# CC3200_Breakout.net
KiCad netlist of a schematic drawn in EAGLE
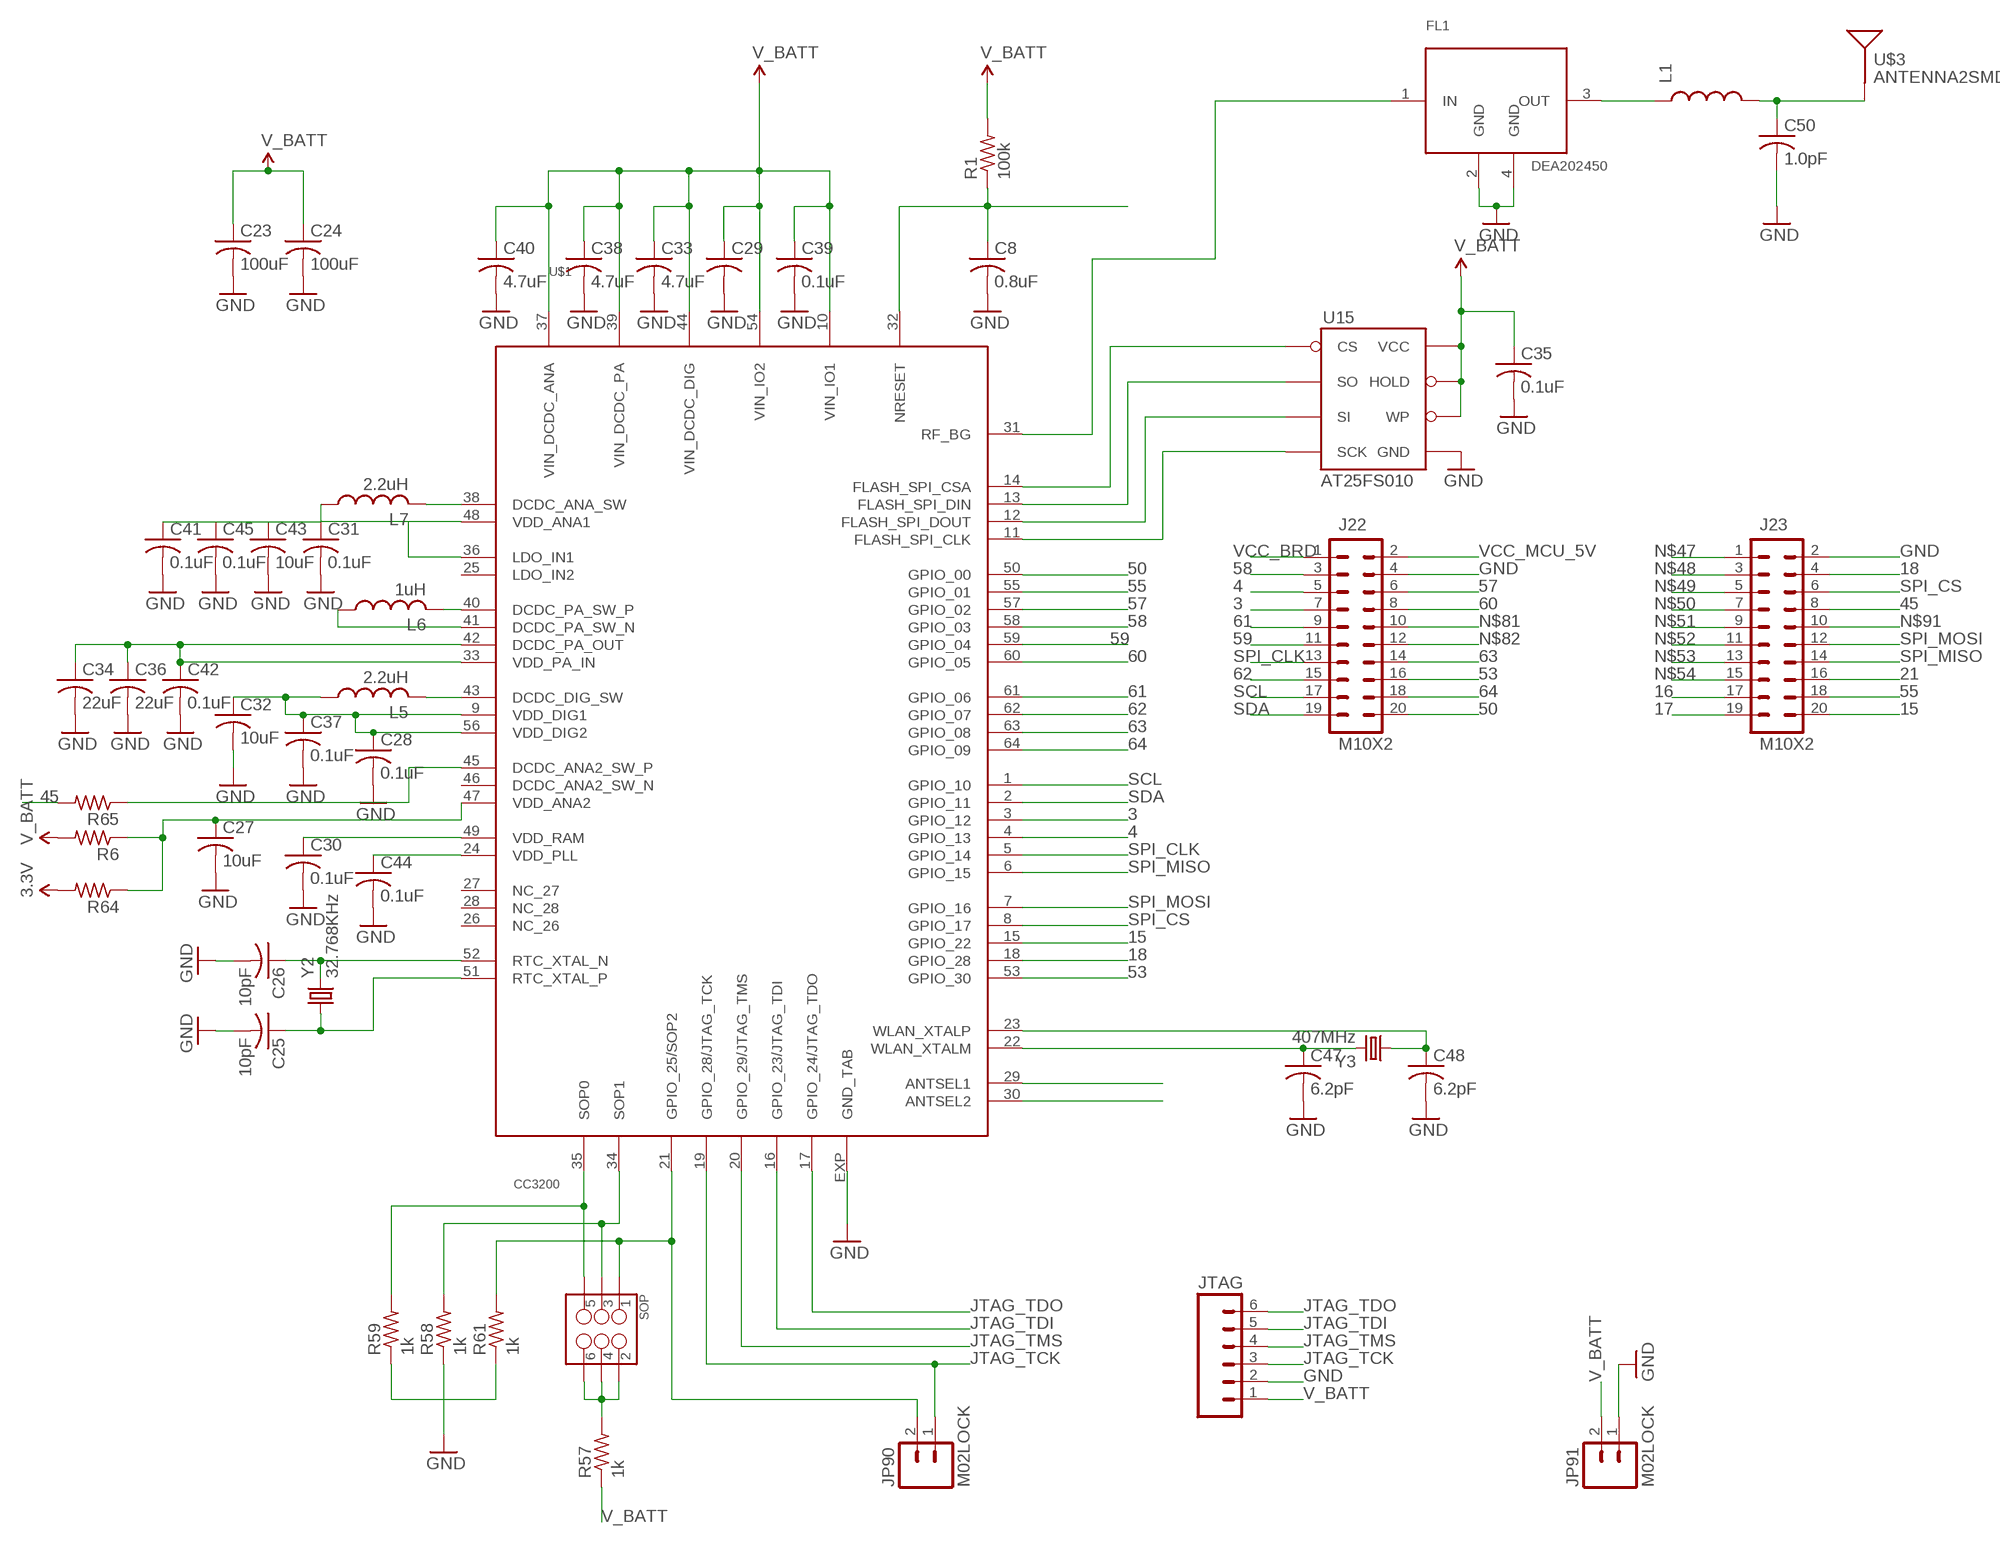
[diagram p0: schematic, sheet 1]

(export (version "E")
  (design (tool "Eeschema 10.0.6"))
  (components
    (comp (ref "C8")
      (value "0.8uF")
      (footprint "eagle-import:C0402K")
      (libsource (lib "eagle-import") (part "C-USC0402K"))
    )
    (comp (ref "C23")
      (value "100uF")
      (footprint "eagle-import:C0402K")
      (libsource (lib "eagle-import") (part "C-USC0402K"))
    )
    (comp (ref "C24")
      (value "100uF")
      (footprint "eagle-import:C0402K")
      (libsource (lib "eagle-import") (part "C-USC0402K"))
    )
    (comp (ref "C25")
      (value "10pF")
      (footprint "eagle-import:C0402K")
      (libsource (lib "eagle-import") (part "C-USC0402K"))
    )
    (comp (ref "C26")
      (value "10pF")
      (footprint "eagle-import:C0402K")
      (libsource (lib "eagle-import") (part "C-USC0402K"))
    )
    (comp (ref "C27")
      (value "10uF")
      (footprint "eagle-import:C0402K")
      (libsource (lib "eagle-import") (part "C-USC0402K"))
    )
    (comp (ref "C28")
      (value "0.1uF")
      (footprint "eagle-import:C0402K")
      (libsource (lib "eagle-import") (part "C-USC0402K"))
    )
    (comp (ref "C29")
      (value "C-USC0402K")
      (footprint "eagle-import:C0402K")
      (libsource (lib "eagle-import") (part "C-USC0402K"))
    )
    (comp (ref "C30")
      (value "0.1uF")
      (footprint "eagle-import:C0402K")
      (libsource (lib "eagle-import") (part "C-USC0402K"))
    )
    (comp (ref "C31")
      (value "0.1uF")
      (footprint "eagle-import:C0402K")
      (libsource (lib "eagle-import") (part "C-USC0402K"))
    )
    (comp (ref "C32")
      (value "10uF")
      (footprint "eagle-import:C0402K")
      (libsource (lib "eagle-import") (part "C-USC0402K"))
    )
    (comp (ref "C33")
      (value "4.7uF")
      (footprint "eagle-import:C0402K")
      (libsource (lib "eagle-import") (part "C-USC0402K"))
    )
    (comp (ref "C34")
      (value "22uF")
      (footprint "eagle-import:C0402K")
      (libsource (lib "eagle-import") (part "C-USC0402K"))
    )
    (comp (ref "C35")
      (value "0.1uF")
      (footprint "eagle-import:C0402K")
      (libsource (lib "eagle-import") (part "C-USC0402K"))
    )
    (comp (ref "C36")
      (value "22uF")
      (footprint "eagle-import:C0402K")
      (libsource (lib "eagle-import") (part "C-USC0402K"))
    )
    (comp (ref "C37")
      (value "0.1uF")
      (footprint "eagle-import:C0402K")
      (libsource (lib "eagle-import") (part "C-USC0402K"))
    )
    (comp (ref "C38")
      (value "4.7uF")
      (footprint "eagle-import:C0402K")
      (libsource (lib "eagle-import") (part "C-USC0402K"))
    )
    (comp (ref "C39")
      (value "0.1uF")
      (footprint "eagle-import:C0402K")
      (libsource (lib "eagle-import") (part "C-USC0402K"))
    )
    (comp (ref "C40")
      (value "4.7uF")
      (footprint "eagle-import:C0402K")
      (libsource (lib "eagle-import") (part "C-USC0402K"))
    )
    (comp (ref "C41")
      (value "0.1uF")
      (footprint "eagle-import:C0402K")
      (libsource (lib "eagle-import") (part "C-USC0402K"))
    )
    (comp (ref "C42")
      (value "0.1uF")
      (footprint "eagle-import:C0402K")
      (libsource (lib "eagle-import") (part "C-USC0402K"))
    )
    (comp (ref "C43")
      (value "10uF")
      (footprint "eagle-import:C0402K")
      (libsource (lib "eagle-import") (part "C-USC0402K"))
    )
    (comp (ref "C44")
      (value "0.1uF")
      (footprint "eagle-import:C0402K")
      (libsource (lib "eagle-import") (part "C-USC0402K"))
    )
    (comp (ref "C45")
      (value "0.1uF")
      (footprint "eagle-import:C0402K")
      (libsource (lib "eagle-import") (part "C-USC0402K"))
    )
    (comp (ref "C47")
      (value "6.2pF")
      (footprint "eagle-import:C0402K")
      (libsource (lib "eagle-import") (part "C-USC0402K"))
    )
    (comp (ref "C48")
      (value "6.2pF")
      (footprint "eagle-import:C0402K")
      (libsource (lib "eagle-import") (part "C-USC0402K"))
    )
    (comp (ref "C50")
      (value "1.0pF")
      (footprint "eagle-import:C0402K")
      (libsource (lib "eagle-import") (part "C-USC0402K"))
    )
    (comp (ref "FL1")
      (value "DEA202450")
      (footprint "eagle-import:DEA202450")
      (libsource (lib "eagle-import") (part "DEA202450"))
    )
    (comp (ref "J22")
      (value "M10X2")
      (footprint "eagle-import:2X10")
      (libsource (lib "eagle-import") (part "M10X2"))
    )
    (comp (ref "J23")
      (value "M10X2")
      (footprint "eagle-import:2X10")
      (libsource (lib "eagle-import") (part "M10X2"))
    )
    (comp (ref "JP90")
      (value "M02LOCK")
      (footprint "eagle-import:1X02_LOCK")
      (libsource (lib "eagle-import") (part "M02LOCK"))
    )
    (comp (ref "JP91")
      (value "M02LOCK")
      (footprint "eagle-import:1X02_LOCK")
      (libsource (lib "eagle-import") (part "M02LOCK"))
    )
    (comp (ref "JTAG")
      (value "M06SILK_FEMALE_PTH")
      (footprint "eagle-import:1X06")
      (libsource (lib "eagle-import") (part "M06SILK_FEMALE_PTH"))
    )
    (comp (ref "L1")
      (value "INDUCTOR-SPARKFUN0402")
      (footprint "eagle-import:C0402")
      (libsource (lib "eagle-import") (part "INDUCTOR-SPARKFUN0402"))
    )
    (comp (ref "L5")
      (value "2.2uH")
      (footprint "eagle-import:L2012C")
      (libsource (lib "eagle-import") (part "L-USL2012C"))
    )
    (comp (ref "L6")
      (value "1uH")
      (footprint "eagle-import:L2012C")
      (libsource (lib "eagle-import") (part "L-USL2012C"))
    )
    (comp (ref "L7")
      (value "2.2uH")
      (footprint "eagle-import:L2012C")
      (libsource (lib "eagle-import") (part "L-USL2012C"))
    )
    (comp (ref "R1")
      (value "100k")
      (footprint "eagle-import:R0402")
      (libsource (lib "eagle-import") (part "R-US_R0402"))
    )
    (comp (ref "R6")
      (value "R-US_R0402")
      (footprint "eagle-import:R0402")
      (libsource (lib "eagle-import") (part "R-US_R0402"))
    )
    (comp (ref "R57")
      (value "1k")
      (footprint "eagle-import:R0402")
      (libsource (lib "eagle-import") (part "R-US_R0402"))
    )
    (comp (ref "R58")
      (value "1k")
      (footprint "eagle-import:R0402")
      (libsource (lib "eagle-import") (part "R-US_R0402"))
    )
    (comp (ref "R59")
      (value "1k")
      (footprint "eagle-import:R0402")
      (libsource (lib "eagle-import") (part "R-US_R0402"))
    )
    (comp (ref "R61")
      (value "1k")
      (footprint "eagle-import:R0402")
      (libsource (lib "eagle-import") (part "R-US_R0402"))
    )
    (comp (ref "R64")
      (value "R-US_R0402")
      (footprint "eagle-import:R0402")
      (libsource (lib "eagle-import") (part "R-US_R0402"))
    )
    (comp (ref "R65")
      (value "R-US_R0402")
      (footprint "eagle-import:R0402")
      (libsource (lib "eagle-import") (part "R-US_R0402"))
    )
    (comp (ref "SOP")
      (value "M03X22X3_SILK_MALE_PTH")
      (footprint "eagle-import:2X3")
      (libsource (lib "eagle-import") (part "M03X22X3_SILK_MALE_PTH"))
    )
    (comp (ref "U$1")
      (value "CC3200")
      (footprint "eagle-import:PVQFN-N64")
      (libsource (lib "eagle-import") (part "CC3200"))
    )
    (comp (ref "U$3")
      (value "ANTENNA2SMD")
      (footprint "eagle-import:ANTENNA-CHIP2")
      (libsource (lib "eagle-import") (part "ANTENNA2SMD"))
    )
    (comp (ref "U15")
      (value "AT25FS010")
      (footprint "eagle-import:SO08WIDE")
      (libsource (lib "eagle-import") (part "AT25FS010"))
    )
    (comp (ref "Y2")
      (value "32.768KHz")
      (footprint "eagle-import:CRYSTAL-SMD-5X3")
      (libsource (lib "eagle-import") (part "CRYSTAL5X3"))
    )
    (comp (ref "Y3")
      (value "407MHz")
      (footprint "eagle-import:CRYSTAL-SMD-5X3")
      (libsource (lib "eagle-import") (part "CRYSTAL5X3"))
    )
  )
  (nets
    (net (code "1") (name "/3") (class "Default")
      (node (ref "J22") (pin "7") (pinfunction "7_7") (pintype "passive"))
      (node (ref "U$1") (pin "3") (pinfunction "GPIO_12_3") (pintype "bidirectional"))
    )
    (net (code "2") (name "/4") (class "Default")
      (node (ref "J22") (pin "5") (pinfunction "5_5") (pintype "passive"))
      (node (ref "U$1") (pin "4") (pinfunction "GPIO_13_4") (pintype "bidirectional"))
    )
    (net (code "3") (name "/15") (class "Default")
      (node (ref "J23") (pin "20") (pinfunction "20_20") (pintype "passive"))
      (node (ref "U$1") (pin "15") (pinfunction "GPIO_22_15") (pintype "bidirectional"))
    )
    (net (code "4") (name "/16") (class "Default")
      (node (ref "J23") (pin "17") (pinfunction "17_17") (pintype "passive"))
    )
    (net (code "5") (name "/17") (class "Default")
      (node (ref "J23") (pin "19") (pinfunction "19_19") (pintype "passive"))
    )
    (net (code "6") (name "/18") (class "Default")
      (node (ref "J23") (pin "4") (pinfunction "4_4") (pintype "passive"))
      (node (ref "U$1") (pin "18") (pinfunction "GPIO_28_18") (pintype "bidirectional"))
    )
    (net (code "7") (name "/21") (class "Default")
      (node (ref "J23") (pin "16") (pinfunction "16_16") (pintype "passive"))
    )
    (net (code "8") (name "/45") (class "Default")
      (node (ref "J23") (pin "8") (pinfunction "8_8") (pintype "passive"))
      (node (ref "R65") (pin "2") (pinfunction "2_2") (pintype "passive"))
    )
    (net (code "9") (name "/50") (class "Default")
      (node (ref "J22") (pin "20") (pinfunction "20_20") (pintype "passive"))
      (node (ref "U$1") (pin "50") (pinfunction "GPIO_00_50") (pintype "bidirectional"))
    )
    (net (code "10") (name "/53") (class "Default")
      (node (ref "J22") (pin "16") (pinfunction "16_16") (pintype "passive"))
      (node (ref "U$1") (pin "53") (pinfunction "GPIO_30_53") (pintype "bidirectional"))
    )
    (net (code "11") (name "/55") (class "Default")
      (node (ref "J23") (pin "18") (pinfunction "18_18") (pintype "passive"))
      (node (ref "U$1") (pin "55") (pinfunction "GPIO_01_55") (pintype "bidirectional"))
    )
    (net (code "12") (name "/57") (class "Default")
      (node (ref "J22") (pin "6") (pinfunction "6_6") (pintype "passive"))
      (node (ref "U$1") (pin "57") (pinfunction "GPIO_02_57") (pintype "bidirectional"))
    )
    (net (code "13") (name "/58") (class "Default")
      (node (ref "J22") (pin "3") (pinfunction "3_3") (pintype "passive"))
      (node (ref "U$1") (pin "58") (pinfunction "GPIO_03_58") (pintype "bidirectional"))
    )
    (net (code "14") (name "/59") (class "Default")
      (node (ref "J22") (pin "11") (pinfunction "11_11") (pintype "passive"))
      (node (ref "U$1") (pin "59") (pinfunction "GPIO_04_59") (pintype "bidirectional"))
    )
    (net (code "15") (name "/60") (class "Default")
      (node (ref "J22") (pin "8") (pinfunction "8_8") (pintype "passive"))
      (node (ref "U$1") (pin "60") (pinfunction "GPIO_05_60") (pintype "bidirectional"))
    )
    (net (code "16") (name "/61") (class "Default")
      (node (ref "J22") (pin "9") (pinfunction "9_9") (pintype "passive"))
      (node (ref "U$1") (pin "61") (pinfunction "GPIO_06_61") (pintype "bidirectional"))
    )
    (net (code "17") (name "/62") (class "Default")
      (node (ref "J22") (pin "15") (pinfunction "15_15") (pintype "passive"))
      (node (ref "U$1") (pin "62") (pinfunction "GPIO_07_62") (pintype "bidirectional"))
    )
    (net (code "18") (name "/63") (class "Default")
      (node (ref "J22") (pin "14") (pinfunction "14_14") (pintype "passive"))
      (node (ref "U$1") (pin "63") (pinfunction "GPIO_08_63") (pintype "bidirectional"))
    )
    (net (code "19") (name "/64") (class "Default")
      (node (ref "J22") (pin "18") (pinfunction "18_18") (pintype "passive"))
      (node (ref "U$1") (pin "64") (pinfunction "GPIO_09_64") (pintype "bidirectional"))
    )
    (net (code "20") (name "/JTAG_TCK") (class "Default")
      (node (ref "JP90") (pin "1") (pinfunction "1_1") (pintype "passive"))
      (node (ref "JTAG") (pin "3") (pinfunction "3_3") (pintype "passive"))
      (node (ref "U$1") (pin "19") (pinfunction "GPIO_28/JTAG_TCK_19") (pintype "bidirectional"))
    )
    (net (code "21") (name "/JTAG_TDI") (class "Default")
      (node (ref "JTAG") (pin "5") (pinfunction "5_5") (pintype "passive"))
      (node (ref "U$1") (pin "16") (pinfunction "GPIO_23/JTAG_TDI_16") (pintype "bidirectional"))
    )
    (net (code "22") (name "/JTAG_TDO") (class "Default")
      (node (ref "JTAG") (pin "6") (pinfunction "6_6") (pintype "passive"))
      (node (ref "U$1") (pin "17") (pinfunction "GPIO_24/JTAG_TDO_17") (pintype "bidirectional"))
    )
    (net (code "23") (name "/JTAG_TMS") (class "Default")
      (node (ref "JTAG") (pin "4") (pinfunction "4_4") (pintype "passive"))
      (node (ref "U$1") (pin "20") (pinfunction "GPIO_29/JTAG_TMS_20") (pintype "bidirectional"))
    )
    (net (code "24") (name "/N$47") (class "Default")
      (node (ref "J23") (pin "1") (pinfunction "1_1") (pintype "passive"))
    )
    (net (code "25") (name "/N$48") (class "Default")
      (node (ref "J23") (pin "3") (pinfunction "3_3") (pintype "passive"))
    )
    (net (code "26") (name "/N$49") (class "Default")
      (node (ref "J23") (pin "5") (pinfunction "5_5") (pintype "passive"))
    )
    (net (code "27") (name "/N$50") (class "Default")
      (node (ref "J23") (pin "7") (pinfunction "7_7") (pintype "passive"))
    )
    (net (code "28") (name "/N$51") (class "Default")
      (node (ref "J23") (pin "9") (pinfunction "9_9") (pintype "passive"))
    )
    (net (code "29") (name "/N$52") (class "Default")
      (node (ref "J23") (pin "11") (pinfunction "11_11") (pintype "passive"))
    )
    (net (code "30") (name "/N$53") (class "Default")
      (node (ref "J23") (pin "13") (pinfunction "13_13") (pintype "passive"))
    )
    (net (code "31") (name "/N$54") (class "Default")
      (node (ref "J23") (pin "15") (pinfunction "15_15") (pintype "passive"))
    )
    (net (code "32") (name "/N$81") (class "Default")
      (node (ref "J22") (pin "10") (pinfunction "10_10") (pintype "passive"))
    )
    (net (code "33") (name "/N$82") (class "Default")
      (node (ref "J22") (pin "12") (pinfunction "12_12") (pintype "passive"))
    )
    (net (code "34") (name "/N$91") (class "Default")
      (node (ref "J23") (pin "10") (pinfunction "10_10") (pintype "passive"))
    )
    (net (code "35") (name "/SCL") (class "Default")
      (node (ref "J22") (pin "17") (pinfunction "17_17") (pintype "passive"))
      (node (ref "U$1") (pin "1") (pinfunction "GPIO_10_1") (pintype "bidirectional"))
    )
    (net (code "36") (name "/SDA") (class "Default")
      (node (ref "J22") (pin "19") (pinfunction "19_19") (pintype "passive"))
      (node (ref "U$1") (pin "2") (pinfunction "GPIO_11_2") (pintype "bidirectional"))
    )
    (net (code "37") (name "/SPI_CLK") (class "Default")
      (node (ref "J22") (pin "13") (pinfunction "13_13") (pintype "passive"))
      (node (ref "U$1") (pin "5") (pinfunction "GPIO_14_5") (pintype "bidirectional"))
    )
    (net (code "38") (name "/SPI_CS") (class "Default")
      (node (ref "J23") (pin "6") (pinfunction "6_6") (pintype "passive"))
      (node (ref "U$1") (pin "8") (pinfunction "GPIO_17_8") (pintype "bidirectional"))
    )
    (net (code "39") (name "/SPI_MISO") (class "Default")
      (node (ref "J23") (pin "14") (pinfunction "14_14") (pintype "passive"))
      (node (ref "U$1") (pin "6") (pinfunction "GPIO_15_6") (pintype "bidirectional"))
    )
    (net (code "40") (name "/SPI_MOSI") (class "Default")
      (node (ref "J23") (pin "12") (pinfunction "12_12") (pintype "passive"))
      (node (ref "U$1") (pin "7") (pinfunction "GPIO_16_7") (pintype "bidirectional"))
    )
    (net (code "41") (name "/VCC_BRD") (class "Default")
      (node (ref "J22") (pin "1") (pinfunction "1_1") (pintype "passive"))
    )
    (net (code "42") (name "/VCC_MCU_5V") (class "Default")
      (node (ref "J22") (pin "2") (pinfunction "2_2") (pintype "passive"))
    )
    (net (code "43") (name "3.3V") (class "Default")
      (node (ref "R64") (pin "2") (pinfunction "2_2") (pintype "passive"))
    )
    (net (code "44") (name "GND") (class "Default")
      (node (ref "C23") (pin "2") (pinfunction "2_2") (pintype "passive"))
      (node (ref "C24") (pin "2") (pinfunction "2_2") (pintype "passive"))
      (node (ref "C25") (pin "2") (pinfunction "2_2") (pintype "passive"))
      (node (ref "C26") (pin "2") (pinfunction "2_2") (pintype "passive"))
      (node (ref "C27") (pin "2") (pinfunction "2_2") (pintype "passive"))
      (node (ref "C28") (pin "2") (pinfunction "2_2") (pintype "passive"))
      (node (ref "C29") (pin "2") (pinfunction "2_2") (pintype "passive"))
      (node (ref "C30") (pin "2") (pinfunction "2_2") (pintype "passive"))
      (node (ref "C31") (pin "2") (pinfunction "2_2") (pintype "passive"))
      (node (ref "C32") (pin "2") (pinfunction "2_2") (pintype "passive"))
      (node (ref "C33") (pin "2") (pinfunction "2_2") (pintype "passive"))
      (node (ref "C34") (pin "2") (pinfunction "2_2") (pintype "passive"))
      (node (ref "C35") (pin "2") (pinfunction "2_2") (pintype "passive"))
      (node (ref "C36") (pin "2") (pinfunction "2_2") (pintype "passive"))
      (node (ref "C37") (pin "2") (pinfunction "2_2") (pintype "passive"))
      (node (ref "C38") (pin "2") (pinfunction "2_2") (pintype "passive"))
      (node (ref "C39") (pin "2") (pinfunction "2_2") (pintype "passive"))
      (node (ref "C40") (pin "2") (pinfunction "2_2") (pintype "passive"))
      (node (ref "C41") (pin "2") (pinfunction "2_2") (pintype "passive"))
      (node (ref "C42") (pin "2") (pinfunction "2_2") (pintype "passive"))
      (node (ref "C43") (pin "2") (pinfunction "2_2") (pintype "passive"))
      (node (ref "C44") (pin "2") (pinfunction "2_2") (pintype "passive"))
      (node (ref "C45") (pin "2") (pinfunction "2_2") (pintype "passive"))
      (node (ref "C47") (pin "2") (pinfunction "2_2") (pintype "passive"))
      (node (ref "C48") (pin "2") (pinfunction "2_2") (pintype "passive"))
      (node (ref "C50") (pin "1") (pinfunction "1_1") (pintype "passive"))
      (node (ref "C50") (pin "2") (pinfunction "2_2") (pintype "passive"))
      (node (ref "C8") (pin "2") (pinfunction "2_2") (pintype "passive"))
      (node (ref "FL1") (pin "2") (pinfunction "GND_2") (pintype "bidirectional"))
      (node (ref "FL1") (pin "4") (pinfunction "GND_4") (pintype "bidirectional"))
      (node (ref "J22") (pin "4") (pinfunction "4_4") (pintype "passive"))
      (node (ref "J23") (pin "2") (pinfunction "2_2") (pintype "passive"))
      (node (ref "JP91") (pin "1") (pinfunction "1_1") (pintype "passive"))
      (node (ref "JTAG") (pin "2") (pinfunction "2_2") (pintype "passive"))
      (node (ref "L1") (pin "2") (pinfunction "2_2") (pintype "passive"))
      (node (ref "R58") (pin "1") (pinfunction "1_1") (pintype "passive"))
      (node (ref "R59") (pin "1") (pinfunction "1_1") (pintype "passive"))
      (node (ref "R61") (pin "1") (pinfunction "1_1") (pintype "passive"))
      (node (ref "U$1") (pin "EXP") (pinfunction "GND_TAB_EXP") (pintype "bidirectional"))
      (node (ref "U$3") (pin "FEED") (pinfunction "SIGNAL_FEED") (pintype "bidirectional"))
      (node (ref "U15") (pin "4") (pinfunction "GND_4") (pintype "bidirectional"))
    )
    (net (code "45") (name "Net-(FL1-IN)") (class "Default")
      (node (ref "FL1") (pin "1") (pinfunction "IN_1") (pintype "bidirectional"))
      (node (ref "U$1") (pin "31") (pinfunction "RF_BG_31") (pintype "bidirectional"))
    )
    (net (code "46") (name "Net-(FL1-OUT)") (class "Default")
      (node (ref "FL1") (pin "3") (pinfunction "OUT_3") (pintype "bidirectional"))
      (node (ref "L1") (pin "1") (pinfunction "1_1") (pintype "passive"))
    )
    (net (code "47") (name "Net-(R57-Pad2)") (class "Default")
      (node (ref "R57") (pin "2") (pinfunction "2_2") (pintype "passive"))
      (node (ref "SOP") (pin "2") (pinfunction "2_2") (pintype "bidirectional"))
      (node (ref "SOP") (pin "4") (pinfunction "4_4") (pintype "bidirectional"))
      (node (ref "SOP") (pin "6") (pinfunction "6_6") (pintype "bidirectional"))
    )
    (net (code "48") (name "Net-(U$1-DCDC_ANA2_SW_P)") (class "Default")
      (node (ref "R65") (pin "1") (pinfunction "1_1") (pintype "passive"))
      (node (ref "U$1") (pin "45") (pinfunction "DCDC_ANA2_SW_P_45") (pintype "bidirectional"))
    )
    (net (code "49") (name "Net-(U$1-DCDC_ANA_SW)") (class "Default")
      (node (ref "L7") (pin "2") (pinfunction "2_2") (pintype "passive"))
      (node (ref "U$1") (pin "38") (pinfunction "DCDC_ANA_SW_38") (pintype "bidirectional"))
    )
    (net (code "50") (name "Net-(U$1-DCDC_DIG_SW)") (class "Default")
      (node (ref "L5") (pin "2") (pinfunction "2_2") (pintype "passive"))
      (node (ref "U$1") (pin "43") (pinfunction "DCDC_DIG_SW_43") (pintype "bidirectional"))
    )
    (net (code "51") (name "Net-(U$1-DCDC_PA_OUT)") (class "Default")
      (node (ref "C34") (pin "1") (pinfunction "1_1") (pintype "passive"))
      (node (ref "C36") (pin "1") (pinfunction "1_1") (pintype "passive"))
      (node (ref "C42") (pin "1") (pinfunction "1_1") (pintype "passive"))
      (node (ref "U$1") (pin "33") (pinfunction "VDD_PA_IN_33") (pintype "bidirectional"))
      (node (ref "U$1") (pin "42") (pinfunction "DCDC_PA_OUT_42") (pintype "bidirectional"))
    )
    (net (code "52") (name "Net-(U$1-DCDC_PA_SW_N)") (class "Default")
      (node (ref "L6") (pin "1") (pinfunction "1_1") (pintype "passive"))
      (node (ref "U$1") (pin "41") (pinfunction "DCDC_PA_SW_N_41") (pintype "bidirectional"))
    )
    (net (code "53") (name "Net-(U$1-DCDC_PA_SW_P)") (class "Default")
      (node (ref "L6") (pin "2") (pinfunction "2_2") (pintype "passive"))
      (node (ref "U$1") (pin "40") (pinfunction "DCDC_PA_SW_P_40") (pintype "bidirectional"))
    )
    (net (code "54") (name "Net-(U$1-FLASH_SPI_CLK)") (class "Default")
      (node (ref "U$1") (pin "11") (pinfunction "FLASH_SPI_CLK_11") (pintype "bidirectional"))
      (node (ref "U15") (pin "6") (pinfunction "SCK_6") (pintype "bidirectional"))
    )
    (net (code "55") (name "Net-(U$1-FLASH_SPI_CSA)") (class "Default")
      (node (ref "U$1") (pin "14") (pinfunction "FLASH_SPI_CSA_14") (pintype "bidirectional"))
      (node (ref "U15") (pin "1") (pinfunction "CS_1") (pintype "bidirectional"))
    )
    (net (code "56") (name "Net-(U$1-FLASH_SPI_DIN)") (class "Default")
      (node (ref "U$1") (pin "13") (pinfunction "FLASH_SPI_DIN_13") (pintype "bidirectional"))
      (node (ref "U15") (pin "2") (pinfunction "SO_2") (pintype "bidirectional"))
    )
    (net (code "57") (name "Net-(U$1-FLASH_SPI_DOUT)") (class "Default")
      (node (ref "U$1") (pin "12") (pinfunction "FLASH_SPI_DOUT_12") (pintype "bidirectional"))
      (node (ref "U15") (pin "5") (pinfunction "SI_5") (pintype "bidirectional"))
    )
    (net (code "58") (name "Net-(U$1-GPIO_25{slash}SOP2)") (class "Default")
      (node (ref "JP90") (pin "2") (pinfunction "2_2") (pintype "passive"))
      (node (ref "R61") (pin "2") (pinfunction "2_2") (pintype "passive"))
      (node (ref "SOP") (pin "1") (pinfunction "1_1") (pintype "bidirectional"))
      (node (ref "U$1") (pin "21") (pinfunction "GPIO_25/SOP2_21") (pintype "bidirectional"))
    )
    (net (code "59") (name "Net-(U$1-LDO_IN1)") (class "Default")
      (node (ref "C31") (pin "1") (pinfunction "1_1") (pintype "passive"))
      (node (ref "C41") (pin "1") (pinfunction "1_1") (pintype "passive"))
      (node (ref "C43") (pin "1") (pinfunction "1_1") (pintype "passive"))
      (node (ref "C45") (pin "1") (pinfunction "1_1") (pintype "passive"))
      (node (ref "L7") (pin "1") (pinfunction "1_1") (pintype "passive"))
      (node (ref "U$1") (pin "36") (pinfunction "LDO_IN1_36") (pintype "bidirectional"))
      (node (ref "U$1") (pin "48") (pinfunction "VDD_ANA1_48") (pintype "bidirectional"))
    )
    (net (code "60") (name "Net-(U$1-NRESET)") (class "Default")
      (node (ref "C8") (pin "1") (pinfunction "1_1") (pintype "passive"))
      (node (ref "R1") (pin "1") (pinfunction "1_1") (pintype "passive"))
      (node (ref "U$1") (pin "32") (pinfunction "NRESET_32") (pintype "bidirectional"))
    )
    (net (code "61") (name "Net-(U$1-RTC_XTAL_N)") (class "Default")
      (node (ref "C26") (pin "1") (pinfunction "1_1") (pintype "passive"))
      (node (ref "U$1") (pin "52") (pinfunction "RTC_XTAL_N_52") (pintype "bidirectional"))
      (node (ref "Y2") (pin "3") (pinfunction "2_3") (pintype "passive"))
    )
    (net (code "62") (name "Net-(U$1-RTC_XTAL_P)") (class "Default")
      (node (ref "C25") (pin "1") (pinfunction "1_1") (pintype "passive"))
      (node (ref "U$1") (pin "51") (pinfunction "RTC_XTAL_P_51") (pintype "bidirectional"))
      (node (ref "Y2") (pin "1") (pinfunction "1_1") (pintype "passive"))
    )
    (net (code "63") (name "Net-(U$1-SOP0)") (class "Default")
      (node (ref "R59") (pin "2") (pinfunction "2_2") (pintype "passive"))
      (node (ref "SOP") (pin "5") (pinfunction "5_5") (pintype "bidirectional"))
      (node (ref "U$1") (pin "35") (pinfunction "SOP0_35") (pintype "bidirectional"))
    )
    (net (code "64") (name "Net-(U$1-SOP1)") (class "Default")
      (node (ref "R58") (pin "2") (pinfunction "2_2") (pintype "passive"))
      (node (ref "SOP") (pin "3") (pinfunction "3_3") (pintype "bidirectional"))
      (node (ref "U$1") (pin "34") (pinfunction "SOP1_34") (pintype "bidirectional"))
    )
    (net (code "65") (name "Net-(U$1-VDD_ANA2)") (class "Default")
      (node (ref "C27") (pin "1") (pinfunction "1_1") (pintype "passive"))
      (node (ref "R6") (pin "1") (pinfunction "1_1") (pintype "passive"))
      (node (ref "R64") (pin "1") (pinfunction "1_1") (pintype "passive"))
      (node (ref "U$1") (pin "47") (pinfunction "VDD_ANA2_47") (pintype "bidirectional"))
    )
    (net (code "66") (name "Net-(U$1-VDD_DIG1)") (class "Default")
      (node (ref "C28") (pin "1") (pinfunction "1_1") (pintype "passive"))
      (node (ref "C32") (pin "1") (pinfunction "1_1") (pintype "passive"))
      (node (ref "C37") (pin "1") (pinfunction "1_1") (pintype "passive"))
      (node (ref "L5") (pin "1") (pinfunction "1_1") (pintype "passive"))
      (node (ref "U$1") (pin "56") (pinfunction "VDD_DIG2_56") (pintype "bidirectional"))
      (node (ref "U$1") (pin "9") (pinfunction "VDD_DIG1_9") (pintype "bidirectional"))
    )
    (net (code "67") (name "Net-(U$1-VDD_PLL)") (class "Default")
      (node (ref "C44") (pin "1") (pinfunction "1_1") (pintype "passive"))
      (node (ref "U$1") (pin "24") (pinfunction "VDD_PLL_24") (pintype "bidirectional"))
    )
    (net (code "68") (name "Net-(U$1-VDD_RAM)") (class "Default")
      (node (ref "C30") (pin "1") (pinfunction "1_1") (pintype "passive"))
      (node (ref "U$1") (pin "49") (pinfunction "VDD_RAM_49") (pintype "bidirectional"))
    )
    (net (code "69") (name "Net-(U$1-WLAN_XTALM)") (class "Default")
      (node (ref "C47") (pin "1") (pinfunction "1_1") (pintype "passive"))
      (node (ref "U$1") (pin "22") (pinfunction "WLAN_XTALM_22") (pintype "bidirectional"))
      (node (ref "Y3") (pin "3") (pinfunction "2_3") (pintype "passive"))
    )
    (net (code "70") (name "Net-(U$1-WLAN_XTALP)") (class "Default")
      (node (ref "C48") (pin "1") (pinfunction "1_1") (pintype "passive"))
      (node (ref "U$1") (pin "23") (pinfunction "WLAN_XTALP_23") (pintype "bidirectional"))
      (node (ref "Y3") (pin "1") (pinfunction "1_1") (pintype "passive"))
    )
    (net (code "71") (name "V_BATT") (class "Default")
      (node (ref "C23") (pin "1") (pinfunction "1_1") (pintype "passive"))
      (node (ref "C24") (pin "1") (pinfunction "1_1") (pintype "passive"))
      (node (ref "C29") (pin "1") (pinfunction "1_1") (pintype "passive"))
      (node (ref "C33") (pin "1") (pinfunction "1_1") (pintype "passive"))
      (node (ref "C35") (pin "1") (pinfunction "1_1") (pintype "passive"))
      (node (ref "C38") (pin "1") (pinfunction "1_1") (pintype "passive"))
      (node (ref "C39") (pin "1") (pinfunction "1_1") (pintype "passive"))
      (node (ref "C40") (pin "1") (pinfunction "1_1") (pintype "passive"))
      (node (ref "JP91") (pin "2") (pinfunction "2_2") (pintype "passive"))
      (node (ref "JTAG") (pin "1") (pinfunction "1_1") (pintype "passive"))
      (node (ref "R1") (pin "2") (pinfunction "2_2") (pintype "passive"))
      (node (ref "R57") (pin "1") (pinfunction "1_1") (pintype "passive"))
      (node (ref "R6") (pin "2") (pinfunction "2_2") (pintype "passive"))
      (node (ref "U$1") (pin "10") (pinfunction "VIN_IO1_10") (pintype "bidirectional"))
      (node (ref "U$1") (pin "37") (pinfunction "VIN_DCDC_ANA_37") (pintype "bidirectional"))
      (node (ref "U$1") (pin "39") (pinfunction "VIN_DCDC_PA_39") (pintype "bidirectional"))
      (node (ref "U$1") (pin "44") (pinfunction "VIN_DCDC_DIG_44") (pintype "bidirectional"))
      (node (ref "U$1") (pin "54") (pinfunction "VIN_IO2_54") (pintype "bidirectional"))
      (node (ref "U15") (pin "3") (pinfunction "WP_3") (pintype "bidirectional"))
      (node (ref "U15") (pin "7") (pinfunction "HOLD_7") (pintype "bidirectional"))
      (node (ref "U15") (pin "8") (pinfunction "VCC_8") (pintype "bidirectional"))
    )
    (net (code "72") (name "unconnected-(U$1-ANTSEL1-Pad29)") (class "Default")
      (node (ref "U$1") (pin "29") (pinfunction "ANTSEL1_29") (pintype "bidirectional"))
    )
    (net (code "73") (name "unconnected-(U$1-ANTSEL2-Pad30)") (class "Default")
      (node (ref "U$1") (pin "30") (pinfunction "ANTSEL2_30") (pintype "bidirectional"))
    )
    (net (code "74") (name "unconnected-(U$1-DCDC_ANA2_SW_N-Pad46)") (class "Default")
      (node (ref "U$1") (pin "46") (pinfunction "DCDC_ANA2_SW_N_46") (pintype "bidirectional"))
    )
    (net (code "75") (name "unconnected-(U$1-LDO_IN2-Pad25)") (class "Default")
      (node (ref "U$1") (pin "25") (pinfunction "LDO_IN2_25") (pintype "bidirectional"))
    )
    (net (code "76") (name "unconnected-(U$1-NC_26-Pad26)") (class "Default")
      (node (ref "U$1") (pin "26") (pinfunction "NC_26_26") (pintype "bidirectional"))
    )
    (net (code "77") (name "unconnected-(U$1-NC_27-Pad27)") (class "Default")
      (node (ref "U$1") (pin "27") (pinfunction "NC_27_27") (pintype "bidirectional"))
    )
    (net (code "78") (name "unconnected-(U$1-NC_28-Pad28)") (class "Default")
      (node (ref "U$1") (pin "28") (pinfunction "NC_28_28") (pintype "bidirectional"))
    )
  )
)
